# shield.net
KiCad netlist of a schematic drawn in EAGLE
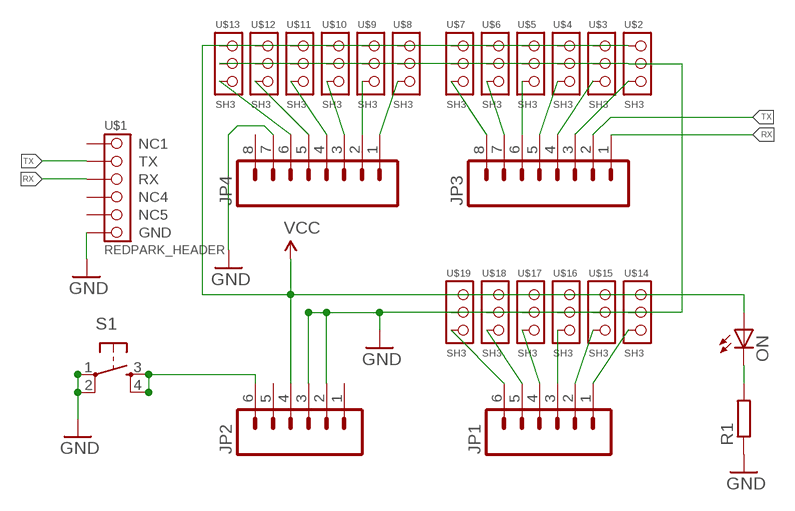
[diagram p0: schematic, sheet 1]

(export (version "E")
  (design (tool "Eeschema 10.0.6"))
  (components
    (comp (ref "JP1")
      (value "M06SIP")
      (footprint "eagle-import:1X06")
      (libsource (lib "eagle-import") (part "M06SIP"))
    )
    (comp (ref "JP2")
      (value "M06SIP")
      (footprint "eagle-import:1X06")
      (libsource (lib "eagle-import") (part "M06SIP"))
    )
    (comp (ref "JP3")
      (value "M081X08")
      (footprint "eagle-import:1X08")
      (libsource (lib "eagle-import") (part "M081X08"))
    )
    (comp (ref "JP4")
      (value "M081X08")
      (footprint "eagle-import:1X08")
      (libsource (lib "eagle-import") (part "M081X08"))
    )
    (comp (ref "ON")
      (value "LEDCHIP-LED0805")
      (footprint "eagle-import:CHIP-LED0805")
      (libsource (lib "eagle-import") (part "LEDCHIP-LED0805"))
    )
    (comp (ref "R1")
      (value "R-EU_M0805")
      (footprint "eagle-import:M0805")
      (libsource (lib "eagle-import") (part "R-EU_M0805"))
    )
    (comp (ref "S1")
      (value "TAC_SWITCHPTH")
      (footprint "eagle-import:TACTILE-PTH")
      (libsource (lib "eagle-import") (part "TAC_SWITCHPTH"))
    )
    (comp (ref "U$1")
      (value "REDPARK_HEADER")
      (footprint "eagle-import:REDPARK_HEADER")
      (libsource (lib "eagle-import") (part "REDPARK_HEADER"))
    )
    (comp (ref "U$2")
      (value "SH3")
      (footprint "eagle-import:SH3")
      (libsource (lib "eagle-import") (part "SH3"))
    )
    (comp (ref "U$3")
      (value "SH3")
      (footprint "eagle-import:SH3")
      (libsource (lib "eagle-import") (part "SH3"))
    )
    (comp (ref "U$4")
      (value "SH3")
      (footprint "eagle-import:SH3")
      (libsource (lib "eagle-import") (part "SH3"))
    )
    (comp (ref "U$5")
      (value "SH3")
      (footprint "eagle-import:SH3")
      (libsource (lib "eagle-import") (part "SH3"))
    )
    (comp (ref "U$6")
      (value "SH3")
      (footprint "eagle-import:SH3")
      (libsource (lib "eagle-import") (part "SH3"))
    )
    (comp (ref "U$7")
      (value "SH3")
      (footprint "eagle-import:SH3")
      (libsource (lib "eagle-import") (part "SH3"))
    )
    (comp (ref "U$8")
      (value "SH3")
      (footprint "eagle-import:SH3")
      (libsource (lib "eagle-import") (part "SH3"))
    )
    (comp (ref "U$9")
      (value "SH3")
      (footprint "eagle-import:SH3")
      (libsource (lib "eagle-import") (part "SH3"))
    )
    (comp (ref "U$10")
      (value "SH3")
      (footprint "eagle-import:SH3")
      (libsource (lib "eagle-import") (part "SH3"))
    )
    (comp (ref "U$11")
      (value "SH3")
      (footprint "eagle-import:SH3")
      (libsource (lib "eagle-import") (part "SH3"))
    )
    (comp (ref "U$12")
      (value "SH3")
      (footprint "eagle-import:SH3")
      (libsource (lib "eagle-import") (part "SH3"))
    )
    (comp (ref "U$13")
      (value "SH3")
      (footprint "eagle-import:SH3")
      (libsource (lib "eagle-import") (part "SH3"))
    )
    (comp (ref "U$14")
      (value "SH3")
      (footprint "eagle-import:SH3")
      (libsource (lib "eagle-import") (part "SH3"))
    )
    (comp (ref "U$15")
      (value "SH3")
      (footprint "eagle-import:SH3")
      (libsource (lib "eagle-import") (part "SH3"))
    )
    (comp (ref "U$16")
      (value "SH3")
      (footprint "eagle-import:SH3")
      (libsource (lib "eagle-import") (part "SH3"))
    )
    (comp (ref "U$17")
      (value "SH3")
      (footprint "eagle-import:SH3")
      (libsource (lib "eagle-import") (part "SH3"))
    )
    (comp (ref "U$18")
      (value "SH3")
      (footprint "eagle-import:SH3")
      (libsource (lib "eagle-import") (part "SH3"))
    )
    (comp (ref "U$19")
      (value "SH3")
      (footprint "eagle-import:SH3")
      (libsource (lib "eagle-import") (part "SH3"))
    )
  )
  (nets
    (net (code "1") (name "GND") (class "Default")
      (node (ref "JP2") (pin "2") (pinfunction "2_2") (pintype "passive"))
      (node (ref "JP2") (pin "3") (pinfunction "3_3") (pintype "passive"))
      (node (ref "JP4") (pin "7") (pinfunction "7_7") (pintype "passive"))
      (node (ref "R1") (pin "1") (pinfunction "1_1") (pintype "passive"))
      (node (ref "S1") (pin "1") (pinfunction "1_1") (pintype "passive"))
      (node (ref "S1") (pin "2") (pinfunction "2_2") (pintype "passive"))
      (node (ref "U$1") (pin "6") (pinfunction "GND_6") (pintype "bidirectional"))
      (node (ref "U$10") (pin "-") (pinfunction "2_-") (pintype "bidirectional"))
      (node (ref "U$11") (pin "-") (pinfunction "2_-") (pintype "bidirectional"))
      (node (ref "U$12") (pin "-") (pinfunction "2_-") (pintype "bidirectional"))
      (node (ref "U$13") (pin "-") (pinfunction "2_-") (pintype "bidirectional"))
      (node (ref "U$14") (pin "-") (pinfunction "2_-") (pintype "bidirectional"))
      (node (ref "U$15") (pin "-") (pinfunction "2_-") (pintype "bidirectional"))
      (node (ref "U$16") (pin "-") (pinfunction "2_-") (pintype "bidirectional"))
      (node (ref "U$17") (pin "-") (pinfunction "2_-") (pintype "bidirectional"))
      (node (ref "U$18") (pin "-") (pinfunction "2_-") (pintype "bidirectional"))
      (node (ref "U$19") (pin "-") (pinfunction "2_-") (pintype "bidirectional"))
      (node (ref "U$2") (pin "-") (pinfunction "2_-") (pintype "bidirectional"))
      (node (ref "U$3") (pin "-") (pinfunction "2_-") (pintype "bidirectional"))
      (node (ref "U$4") (pin "-") (pinfunction "2_-") (pintype "bidirectional"))
      (node (ref "U$5") (pin "-") (pinfunction "2_-") (pintype "bidirectional"))
      (node (ref "U$6") (pin "-") (pinfunction "2_-") (pintype "bidirectional"))
      (node (ref "U$7") (pin "-") (pinfunction "2_-") (pintype "bidirectional"))
      (node (ref "U$8") (pin "-") (pinfunction "2_-") (pintype "bidirectional"))
      (node (ref "U$9") (pin "-") (pinfunction "2_-") (pintype "bidirectional"))
    )
    (net (code "2") (name "Net-(JP2-Pad6)") (class "Default")
      (node (ref "JP2") (pin "6") (pinfunction "6_6") (pintype "passive"))
      (node (ref "S1") (pin "3") (pinfunction "3_3") (pintype "passive"))
      (node (ref "S1") (pin "4") (pinfunction "4_4") (pintype "passive"))
    )
    (net (code "3") (name "Net-(ON-PadC)") (class "Default")
      (node (ref "ON") (pin "C") (pinfunction "C_C") (pintype "passive"))
      (node (ref "R1") (pin "2") (pinfunction "2_2") (pintype "passive"))
    )
    (net (code "4") (name "Net-(U$2-3)") (class "Default")
      (node (ref "JP3") (pin "3") (pinfunction "3_3") (pintype "passive"))
      (node (ref "U$2") (pin "+") (pinfunction "3_+") (pintype "bidirectional"))
    )
    (net (code "5") (name "Net-(U$3-3)") (class "Default")
      (node (ref "JP3") (pin "4") (pinfunction "4_4") (pintype "passive"))
      (node (ref "U$3") (pin "+") (pinfunction "3_+") (pintype "bidirectional"))
    )
    (net (code "6") (name "Net-(U$4-3)") (class "Default")
      (node (ref "JP3") (pin "5") (pinfunction "5_5") (pintype "passive"))
      (node (ref "U$4") (pin "+") (pinfunction "3_+") (pintype "bidirectional"))
    )
    (net (code "7") (name "Net-(U$5-3)") (class "Default")
      (node (ref "JP3") (pin "6") (pinfunction "6_6") (pintype "passive"))
      (node (ref "U$5") (pin "+") (pinfunction "3_+") (pintype "bidirectional"))
    )
    (net (code "8") (name "Net-(U$6-3)") (class "Default")
      (node (ref "JP3") (pin "7") (pinfunction "7_7") (pintype "passive"))
      (node (ref "U$6") (pin "+") (pinfunction "3_+") (pintype "bidirectional"))
    )
    (net (code "9") (name "Net-(U$7-3)") (class "Default")
      (node (ref "JP3") (pin "8") (pinfunction "8_8") (pintype "passive"))
      (node (ref "U$7") (pin "+") (pinfunction "3_+") (pintype "bidirectional"))
    )
    (net (code "10") (name "Net-(U$8-3)") (class "Default")
      (node (ref "JP4") (pin "1") (pinfunction "1_1") (pintype "passive"))
      (node (ref "U$8") (pin "+") (pinfunction "3_+") (pintype "bidirectional"))
    )
    (net (code "11") (name "Net-(U$9-3)") (class "Default")
      (node (ref "JP4") (pin "2") (pinfunction "2_2") (pintype "passive"))
      (node (ref "U$9") (pin "+") (pinfunction "3_+") (pintype "bidirectional"))
    )
    (net (code "12") (name "Net-(U$10-3)") (class "Default")
      (node (ref "JP4") (pin "3") (pinfunction "3_3") (pintype "passive"))
      (node (ref "U$10") (pin "+") (pinfunction "3_+") (pintype "bidirectional"))
    )
    (net (code "13") (name "Net-(U$11-3)") (class "Default")
      (node (ref "JP4") (pin "4") (pinfunction "4_4") (pintype "passive"))
      (node (ref "U$11") (pin "+") (pinfunction "3_+") (pintype "bidirectional"))
    )
    (net (code "14") (name "Net-(U$12-3)") (class "Default")
      (node (ref "JP4") (pin "5") (pinfunction "5_5") (pintype "passive"))
      (node (ref "U$12") (pin "+") (pinfunction "3_+") (pintype "bidirectional"))
    )
    (net (code "15") (name "Net-(U$13-3)") (class "Default")
      (node (ref "JP4") (pin "6") (pinfunction "6_6") (pintype "passive"))
      (node (ref "U$13") (pin "+") (pinfunction "3_+") (pintype "bidirectional"))
    )
    (net (code "16") (name "Net-(U$14-3)") (class "Default")
      (node (ref "JP1") (pin "1") (pinfunction "1_1") (pintype "passive"))
      (node (ref "U$14") (pin "+") (pinfunction "3_+") (pintype "bidirectional"))
    )
    (net (code "17") (name "Net-(U$15-3)") (class "Default")
      (node (ref "JP1") (pin "2") (pinfunction "2_2") (pintype "passive"))
      (node (ref "U$15") (pin "+") (pinfunction "3_+") (pintype "bidirectional"))
    )
    (net (code "18") (name "Net-(U$16-3)") (class "Default")
      (node (ref "JP1") (pin "3") (pinfunction "3_3") (pintype "passive"))
      (node (ref "U$16") (pin "+") (pinfunction "3_+") (pintype "bidirectional"))
    )
    (net (code "19") (name "Net-(U$17-3)") (class "Default")
      (node (ref "JP1") (pin "4") (pinfunction "4_4") (pintype "passive"))
      (node (ref "U$17") (pin "+") (pinfunction "3_+") (pintype "bidirectional"))
    )
    (net (code "20") (name "Net-(U$18-3)") (class "Default")
      (node (ref "JP1") (pin "5") (pinfunction "5_5") (pintype "passive"))
      (node (ref "U$18") (pin "+") (pinfunction "3_+") (pintype "bidirectional"))
    )
    (net (code "21") (name "Net-(U$19-3)") (class "Default")
      (node (ref "JP1") (pin "6") (pinfunction "6_6") (pintype "passive"))
      (node (ref "U$19") (pin "+") (pinfunction "3_+") (pintype "bidirectional"))
    )
    (net (code "22") (name "RX") (class "Default")
      (node (ref "JP3") (pin "1") (pinfunction "1_1") (pintype "passive"))
      (node (ref "U$1") (pin "3") (pinfunction "RX_3") (pintype "bidirectional"))
    )
    (net (code "23") (name "TX") (class "Default")
      (node (ref "JP3") (pin "2") (pinfunction "2_2") (pintype "passive"))
      (node (ref "U$1") (pin "2") (pinfunction "TX_2") (pintype "bidirectional"))
    )
    (net (code "24") (name "VCC") (class "Default")
      (node (ref "JP2") (pin "4") (pinfunction "4_4") (pintype "passive"))
      (node (ref "ON") (pin "A") (pinfunction "A_A") (pintype "passive"))
      (node (ref "U$10") (pin "S") (pinfunction "1_S") (pintype "bidirectional"))
      (node (ref "U$11") (pin "S") (pinfunction "1_S") (pintype "bidirectional"))
      (node (ref "U$12") (pin "S") (pinfunction "1_S") (pintype "bidirectional"))
      (node (ref "U$13") (pin "S") (pinfunction "1_S") (pintype "bidirectional"))
      (node (ref "U$14") (pin "S") (pinfunction "1_S") (pintype "bidirectional"))
      (node (ref "U$15") (pin "S") (pinfunction "1_S") (pintype "bidirectional"))
      (node (ref "U$16") (pin "S") (pinfunction "1_S") (pintype "bidirectional"))
      (node (ref "U$17") (pin "S") (pinfunction "1_S") (pintype "bidirectional"))
      (node (ref "U$18") (pin "S") (pinfunction "1_S") (pintype "bidirectional"))
      (node (ref "U$19") (pin "S") (pinfunction "1_S") (pintype "bidirectional"))
      (node (ref "U$2") (pin "S") (pinfunction "1_S") (pintype "bidirectional"))
      (node (ref "U$3") (pin "S") (pinfunction "1_S") (pintype "bidirectional"))
      (node (ref "U$4") (pin "S") (pinfunction "1_S") (pintype "bidirectional"))
      (node (ref "U$5") (pin "S") (pinfunction "1_S") (pintype "bidirectional"))
      (node (ref "U$6") (pin "S") (pinfunction "1_S") (pintype "bidirectional"))
      (node (ref "U$7") (pin "S") (pinfunction "1_S") (pintype "bidirectional"))
      (node (ref "U$8") (pin "S") (pinfunction "1_S") (pintype "bidirectional"))
      (node (ref "U$9") (pin "S") (pinfunction "1_S") (pintype "bidirectional"))
    )
    (net (code "25") (name "unconnected-(JP2-Pad1)") (class "Default")
      (node (ref "JP2") (pin "1") (pinfunction "1_1") (pintype "passive"))
    )
    (net (code "26") (name "unconnected-(JP2-Pad5)") (class "Default")
      (node (ref "JP2") (pin "5") (pinfunction "5_5") (pintype "passive"))
    )
    (net (code "27") (name "unconnected-(JP4-Pad8)") (class "Default")
      (node (ref "JP4") (pin "8") (pinfunction "8_8") (pintype "passive"))
    )
    (net (code "28") (name "unconnected-(U$1-NC1-Pad1)") (class "Default")
      (node (ref "U$1") (pin "1") (pinfunction "NC1_1") (pintype "bidirectional"))
    )
    (net (code "29") (name "unconnected-(U$1-NC4-Pad4)") (class "Default")
      (node (ref "U$1") (pin "4") (pinfunction "NC4_4") (pintype "bidirectional"))
    )
    (net (code "30") (name "unconnected-(U$1-NC5-Pad5)") (class "Default")
      (node (ref "U$1") (pin "5") (pinfunction "NC5_5") (pintype "bidirectional"))
    )
  )
)
